# lighthouse_sensor.net
KiCad netlist of a schematic drawn in Altium Designer
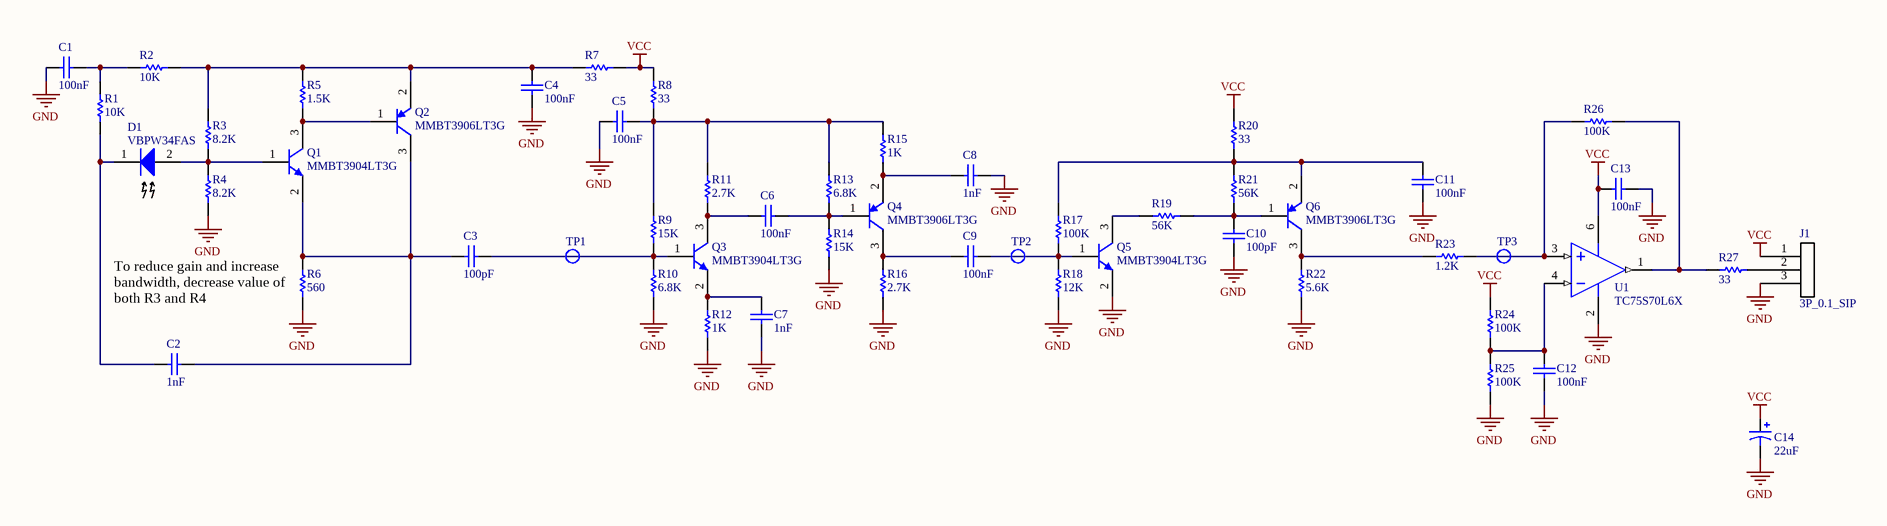
[diagram p0: lighthouse_sensor.SchDoc]

(export (version "E")
  (design (tool "Eeschema 10.0.6"))
  (components
    (comp (ref "C1")
      (value "100nF")
      (footprint "0603")
      (description "Ceramic Chip Capacitor - Standard")
      (fields (field (name "Comment") "C0603") (field (name "PUBLISHER") "Altium Limited"))
      (libsource (lib "lighthouse_sensor") (part "C0603"))
    )
    (comp (ref "C2")
      (value "1nF")
      (footprint "0603")
      (description "Ceramic Chip Capacitor - Standard")
      (fields (field (name "Comment") "C0603") (field (name "PUBLISHER") "Altium Limited"))
      (libsource (lib "lighthouse_sensor") (part "C0603"))
    )
    (comp (ref "C3")
      (value "100pF")
      (footprint "0603")
      (description "Ceramic Chip Capacitor - Standard")
      (fields (field (name "Comment") "C0603") (field (name "PUBLISHER") "Altium Limited"))
      (libsource (lib "lighthouse_sensor") (part "C0603"))
    )
    (comp (ref "C4")
      (value "100nF")
      (footprint "0603")
      (description "Ceramic Chip Capacitor - Standard")
      (fields (field (name "Comment") "C0603") (field (name "PUBLISHER") "Altium Limited"))
      (libsource (lib "lighthouse_sensor") (part "C0603"))
    )
    (comp (ref "C5")
      (value "100nF")
      (footprint "0603")
      (description "Ceramic Chip Capacitor - Standard")
      (fields (field (name "Comment") "C0603") (field (name "PUBLISHER") "Altium Limited"))
      (libsource (lib "lighthouse_sensor") (part "C0603"))
    )
    (comp (ref "C6")
      (value "100nF")
      (footprint "0603")
      (description "Ceramic Chip Capacitor - Standard")
      (fields (field (name "Comment") "C0603") (field (name "PUBLISHER") "Altium Limited"))
      (libsource (lib "lighthouse_sensor") (part "C0603"))
    )
    (comp (ref "C7")
      (value "1nF")
      (footprint "0603")
      (description "Ceramic Chip Capacitor - Standard")
      (fields (field (name "Comment") "C0603") (field (name "PUBLISHER") "Altium Limited"))
      (libsource (lib "lighthouse_sensor") (part "C0603"))
    )
    (comp (ref "C8")
      (value "1nF")
      (footprint "0603")
      (description "Ceramic Chip Capacitor - Standard")
      (fields (field (name "Comment") "C0603") (field (name "PUBLISHER") "Altium Limited"))
      (libsource (lib "lighthouse_sensor") (part "C0603"))
    )
    (comp (ref "C9")
      (value "100nF")
      (footprint "0603")
      (description "Ceramic Chip Capacitor - Standard")
      (fields (field (name "Comment") "C0603") (field (name "PUBLISHER") "Altium Limited"))
      (libsource (lib "lighthouse_sensor") (part "C0603"))
    )
    (comp (ref "C10")
      (value "100pF")
      (footprint "0603")
      (description "Ceramic Chip Capacitor - Standard")
      (fields (field (name "Comment") "C0603") (field (name "PUBLISHER") "Altium Limited"))
      (libsource (lib "lighthouse_sensor") (part "C0603"))
    )
    (comp (ref "C11")
      (value "100nF")
      (footprint "0603")
      (description "Ceramic Chip Capacitor - Standard")
      (fields (field (name "Comment") "C0603") (field (name "PUBLISHER") "Altium Limited"))
      (libsource (lib "lighthouse_sensor") (part "C0603"))
    )
    (comp (ref "C12")
      (value "100nF")
      (footprint "0603")
      (description "Ceramic Chip Capacitor - Standard")
      (fields (field (name "Comment") "C0603") (field (name "PUBLISHER") "Altium Limited"))
      (libsource (lib "lighthouse_sensor") (part "C0603"))
    )
    (comp (ref "C13")
      (value "100nF")
      (footprint "0603")
      (description "Ceramic Chip Capacitor - Standard")
      (fields (field (name "Comment") "C0603") (field (name "PUBLISHER") "Altium Limited"))
      (libsource (lib "lighthouse_sensor") (part "C0603"))
    )
    (comp (ref "C14")
      (value "22uF")
      (footprint "Capacitor")
      (fields (field (name "Comment") "Electrolytic Capacitor"))
      (libsource (lib "lighthouse_sensor") (part "Electrolytic Capacitor"))
    )
    (comp (ref "D1")
      (value "VBPW34FAS")
      (footprint "VBPW34FAS")
      (description "Silicon PIN Photodiode")
      (libsource (lib "lighthouse_sensor") (part "VBPW34FAS"))
    )
    (comp (ref "J1")
      (value "3P_0.1_SIP")
      (footprint "3P_0.1_SIP")
      (description "1x3 0.1\" PTH Header")
      (libsource (lib "lighthouse_sensor") (part "3P_0.1_SIP"))
    )
    (comp (ref "Q1")
      (value "MMBT3904LT3G")
      (footprint "ONSC-SOT-23-3-318-08_V")
      (description "General Purpose Transistor, NPN Silicon, 3-Pin SOT-23, Pb-Free, Tape and Reel")
      (fields (field (name "MANUFACTURER") "On Semiconductor"))
      (libsource (lib "lighthouse_sensor") (part "MMBT3904LT3G"))
    )
    (comp (ref "Q2")
      (value "MMBT3906LT3G")
      (footprint "ONSC-SOT-23-3-318-08_V")
      (description "General Purpose Transistor, PNP Silicon, 3-Pin SOT-23, Pb-Free, Tape and Reel")
      (fields (field (name "MANUFACTURER") "On Semiconductor"))
      (libsource (lib "lighthouse_sensor") (part "MMBT3906LT3G"))
    )
    (comp (ref "Q3")
      (value "MMBT3904LT3G")
      (footprint "ONSC-SOT-23-3-318-08_V")
      (description "General Purpose Transistor, NPN Silicon, 3-Pin SOT-23, Pb-Free, Tape and Reel")
      (fields (field (name "MANUFACTURER") "On Semiconductor"))
      (libsource (lib "lighthouse_sensor") (part "MMBT3904LT3G"))
    )
    (comp (ref "Q4")
      (value "MMBT3906LT3G")
      (footprint "ONSC-SOT-23-3-318-08_V")
      (description "General Purpose Transistor, PNP Silicon, 3-Pin SOT-23, Pb-Free, Tape and Reel")
      (fields (field (name "MANUFACTURER") "On Semiconductor"))
      (libsource (lib "lighthouse_sensor") (part "MMBT3906LT3G"))
    )
    (comp (ref "Q5")
      (value "MMBT3904LT3G")
      (footprint "ONSC-SOT-23-3-318-08_V")
      (description "General Purpose Transistor, NPN Silicon, 3-Pin SOT-23, Pb-Free, Tape and Reel")
      (fields (field (name "MANUFACTURER") "On Semiconductor"))
      (libsource (lib "lighthouse_sensor") (part "MMBT3904LT3G"))
    )
    (comp (ref "Q6")
      (value "MMBT3906LT3G")
      (footprint "ONSC-SOT-23-3-318-08_V")
      (description "General Purpose Transistor, PNP Silicon, 3-Pin SOT-23, Pb-Free, Tape and Reel")
      (fields (field (name "MANUFACTURER") "On Semiconductor"))
      (libsource (lib "lighthouse_sensor") (part "MMBT3906LT3G"))
    )
    (comp (ref "R1")
      (value "10K")
      (footprint "3-0603")
      (fields (field (name "PUBLISHER") "Altium Limited"))
      (libsource (lib "lighthouse_sensor") (part "ERJ3EK"))
    )
    (comp (ref "R2")
      (value "10K")
      (footprint "3-0603")
      (fields (field (name "PUBLISHER") "Altium Limited"))
      (libsource (lib "lighthouse_sensor") (part "ERJ3EK"))
    )
    (comp (ref "R3")
      (value "8.2K")
      (footprint "3-0603")
      (fields (field (name "PUBLISHER") "Altium Limited"))
      (libsource (lib "lighthouse_sensor") (part "ERJ3EK"))
    )
    (comp (ref "R4")
      (value "8.2K")
      (footprint "3-0603")
      (fields (field (name "PUBLISHER") "Altium Limited"))
      (libsource (lib "lighthouse_sensor") (part "ERJ3EK"))
    )
    (comp (ref "R5")
      (value "1.5K")
      (footprint "3-0603")
      (fields (field (name "PUBLISHER") "Altium Limited"))
      (libsource (lib "lighthouse_sensor") (part "ERJ3EK"))
    )
    (comp (ref "R6")
      (value "560")
      (footprint "3-0603")
      (fields (field (name "PUBLISHER") "Altium Limited"))
      (libsource (lib "lighthouse_sensor") (part "ERJ3EK"))
    )
    (comp (ref "R7")
      (value "33")
      (footprint "3-0603")
      (fields (field (name "PUBLISHER") "Altium Limited"))
      (libsource (lib "lighthouse_sensor") (part "ERJ3EK"))
    )
    (comp (ref "R8")
      (value "33")
      (footprint "3-0603")
      (fields (field (name "PUBLISHER") "Altium Limited"))
      (libsource (lib "lighthouse_sensor") (part "ERJ3EK"))
    )
    (comp (ref "R9")
      (value "15K")
      (footprint "3-0603")
      (fields (field (name "PUBLISHER") "Altium Limited"))
      (libsource (lib "lighthouse_sensor") (part "ERJ3EK"))
    )
    (comp (ref "R10")
      (value "6.8K")
      (footprint "3-0603")
      (fields (field (name "PUBLISHER") "Altium Limited"))
      (libsource (lib "lighthouse_sensor") (part "ERJ3EK"))
    )
    (comp (ref "R11")
      (value "2.7K")
      (footprint "3-0603")
      (fields (field (name "PUBLISHER") "Altium Limited"))
      (libsource (lib "lighthouse_sensor") (part "ERJ3EK"))
    )
    (comp (ref "R12")
      (value "1K")
      (footprint "3-0603")
      (fields (field (name "PUBLISHER") "Altium Limited"))
      (libsource (lib "lighthouse_sensor") (part "ERJ3EK"))
    )
    (comp (ref "R13")
      (value "6.8K")
      (footprint "3-0603")
      (fields (field (name "PUBLISHER") "Altium Limited"))
      (libsource (lib "lighthouse_sensor") (part "ERJ3EK"))
    )
    (comp (ref "R14")
      (value "15K")
      (footprint "3-0603")
      (fields (field (name "PUBLISHER") "Altium Limited"))
      (libsource (lib "lighthouse_sensor") (part "ERJ3EK"))
    )
    (comp (ref "R15")
      (value "1K")
      (footprint "3-0603")
      (fields (field (name "PUBLISHER") "Altium Limited"))
      (libsource (lib "lighthouse_sensor") (part "ERJ3EK"))
    )
    (comp (ref "R16")
      (value "2.7K")
      (footprint "3-0603")
      (fields (field (name "PUBLISHER") "Altium Limited"))
      (libsource (lib "lighthouse_sensor") (part "ERJ3EK"))
    )
    (comp (ref "R17")
      (value "100K")
      (footprint "3-0603")
      (fields (field (name "PUBLISHER") "Altium Limited"))
      (libsource (lib "lighthouse_sensor") (part "ERJ3EK"))
    )
    (comp (ref "R18")
      (value "12K")
      (footprint "3-0603")
      (fields (field (name "PUBLISHER") "Altium Limited"))
      (libsource (lib "lighthouse_sensor") (part "ERJ3EK"))
    )
    (comp (ref "R19")
      (value "56K")
      (footprint "3-0603")
      (fields (field (name "PUBLISHER") "Altium Limited"))
      (libsource (lib "lighthouse_sensor") (part "ERJ3EK"))
    )
    (comp (ref "R20")
      (value "33")
      (footprint "3-0603")
      (fields (field (name "PUBLISHER") "Altium Limited"))
      (libsource (lib "lighthouse_sensor") (part "ERJ3EK"))
    )
    (comp (ref "R21")
      (value "56K")
      (footprint "3-0603")
      (fields (field (name "PUBLISHER") "Altium Limited"))
      (libsource (lib "lighthouse_sensor") (part "ERJ3EK"))
    )
    (comp (ref "R22")
      (value "5.6K")
      (footprint "3-0603")
      (fields (field (name "PUBLISHER") "Altium Limited"))
      (libsource (lib "lighthouse_sensor") (part "ERJ3EK"))
    )
    (comp (ref "R23")
      (value "1.2K")
      (footprint "3-0603")
      (fields (field (name "PUBLISHER") "Altium Limited"))
      (libsource (lib "lighthouse_sensor") (part "ERJ3EK"))
    )
    (comp (ref "R24")
      (value "100K")
      (footprint "3-0603")
      (fields (field (name "PUBLISHER") "Altium Limited"))
      (libsource (lib "lighthouse_sensor") (part "ERJ3EK"))
    )
    (comp (ref "R25")
      (value "100K")
      (footprint "3-0603")
      (fields (field (name "PUBLISHER") "Altium Limited"))
      (libsource (lib "lighthouse_sensor") (part "ERJ3EK"))
    )
    (comp (ref "R26")
      (value "100K")
      (footprint "3-0603")
      (fields (field (name "PUBLISHER") "Altium Limited"))
      (libsource (lib "lighthouse_sensor") (part "ERJ3EK"))
    )
    (comp (ref "R27")
      (value "33")
      (footprint "3-0603")
      (fields (field (name "PUBLISHER") "Altium Limited"))
      (libsource (lib "lighthouse_sensor") (part "ERJ3EK"))
    )
    (comp (ref "U1")
      (value "TC75S70L6X")
      (footprint "MP6C")
      (description "Single Comparator")
      (libsource (lib "lighthouse_sensor") (part "TC75S70L6X"))
    )
  )
  (nets
    (net (code "1") (name "GND") (class "Default")
      (node (ref "C1") (pin "2") (pinfunction "2_2") (pintype "passive"))
      (node (ref "C10") (pin "2") (pinfunction "2_2") (pintype "passive"))
      (node (ref "C11") (pin "2") (pinfunction "2_2") (pintype "passive"))
      (node (ref "C12") (pin "2") (pinfunction "2_2") (pintype "passive"))
      (node (ref "C13") (pin "1") (pinfunction "1_1") (pintype "passive"))
      (node (ref "C14") (pin "2") (pinfunction "2_2") (pintype "passive"))
      (node (ref "C4") (pin "2") (pinfunction "2_2") (pintype "passive"))
      (node (ref "C5") (pin "2") (pinfunction "2_2") (pintype "passive"))
      (node (ref "C7") (pin "2") (pinfunction "2_2") (pintype "passive"))
      (node (ref "C8") (pin "1") (pinfunction "1_1") (pintype "passive"))
      (node (ref "J1") (pin "3") (pinfunction "3_3") (pintype "passive"))
      (node (ref "Q5") (pin "2") (pinfunction "E_2") (pintype "passive"))
      (node (ref "R10") (pin "1") (pinfunction "1_1") (pintype "passive"))
      (node (ref "R12") (pin "1") (pinfunction "1_1") (pintype "passive"))
      (node (ref "R14") (pin "1") (pinfunction "1_1") (pintype "passive"))
      (node (ref "R16") (pin "1") (pinfunction "1_1") (pintype "passive"))
      (node (ref "R18") (pin "1") (pinfunction "1_1") (pintype "passive"))
      (node (ref "R22") (pin "1") (pinfunction "1_1") (pintype "passive"))
      (node (ref "R25") (pin "1") (pinfunction "1_1") (pintype "passive"))
      (node (ref "R4") (pin "1") (pinfunction "1_1") (pintype "passive"))
      (node (ref "R6") (pin "1") (pinfunction "1_1") (pintype "passive"))
      (node (ref "U1") (pin "2") (pinfunction "VSS_2") (pintype "power_in"))
    )
    (net (code "2") (name "Net-(C1-Pad1)") (class "Default")
      (node (ref "C1") (pin "1") (pinfunction "1_1") (pintype "passive"))
      (node (ref "R1") (pin "2") (pinfunction "2_2") (pintype "passive"))
      (node (ref "R2") (pin "2") (pinfunction "2_2") (pintype "passive"))
    )
    (net (code "3") (name "Net-(C5-Pad1)") (class "Default")
      (node (ref "C5") (pin "1") (pinfunction "1_1") (pintype "passive"))
      (node (ref "R11") (pin "1") (pinfunction "1_1") (pintype "passive"))
      (node (ref "R13") (pin "1") (pinfunction "1_1") (pintype "passive"))
      (node (ref "R15") (pin "1") (pinfunction "1_1") (pintype "passive"))
      (node (ref "R8") (pin "2") (pinfunction "2_2") (pintype "passive"))
      (node (ref "R9") (pin "1") (pinfunction "1_1") (pintype "passive"))
    )
    (net (code "4") (name "Net-(D1-A)") (class "Default")
      (node (ref "D1") (pin "2") (pinfunction "A_2") (pintype "passive"))
      (node (ref "Q1") (pin "1") (pinfunction "B_1") (pintype "passive"))
      (node (ref "R3") (pin "1") (pinfunction "1_1") (pintype "passive"))
      (node (ref "R4") (pin "2") (pinfunction "2_2") (pintype "passive"))
    )
    (net (code "5") (name "Net-(D1-K)") (class "Default")
      (node (ref "C2") (pin "2") (pinfunction "2_2") (pintype "passive"))
      (node (ref "D1") (pin "1") (pinfunction "K_1") (pintype "passive"))
      (node (ref "R1") (pin "1") (pinfunction "1_1") (pintype "passive"))
    )
    (net (code "6") (name "Net-(J1-Pad2)") (class "Default")
      (node (ref "J1") (pin "2") (pinfunction "2_2") (pintype "passive"))
      (node (ref "R27") (pin "1") (pinfunction "1_1") (pintype "passive"))
    )
    (net (code "7") (name "Net-(Q1-C)") (class "Default")
      (node (ref "Q1") (pin "3") (pinfunction "C_3") (pintype "passive"))
      (node (ref "Q2") (pin "1") (pinfunction "B_1") (pintype "passive"))
      (node (ref "R5") (pin "1") (pinfunction "1_1") (pintype "passive"))
    )
    (net (code "8") (name "Net-(Q1-E)") (class "Default")
      (node (ref "C2") (pin "1") (pinfunction "1_1") (pintype "passive"))
      (node (ref "C3") (pin "2") (pinfunction "2_2") (pintype "passive"))
      (node (ref "Q1") (pin "2") (pinfunction "E_2") (pintype "passive"))
      (node (ref "Q2") (pin "3") (pinfunction "C_3") (pintype "passive"))
      (node (ref "R6") (pin "2") (pinfunction "2_2") (pintype "passive"))
    )
    (net (code "9") (name "Net-(Q2-E)") (class "Default")
      (node (ref "C4") (pin "1") (pinfunction "1_1") (pintype "passive"))
      (node (ref "Q2") (pin "2") (pinfunction "E_2") (pintype "passive"))
      (node (ref "R2") (pin "1") (pinfunction "1_1") (pintype "passive"))
      (node (ref "R3") (pin "2") (pinfunction "2_2") (pintype "passive"))
      (node (ref "R5") (pin "2") (pinfunction "2_2") (pintype "passive"))
      (node (ref "R7") (pin "2") (pinfunction "2_2") (pintype "passive"))
    )
    (net (code "10") (name "Net-(Q3-B)") (class "Default")
      (node (ref "C3") (pin "1") (pinfunction "1_1") (pintype "passive"))
      (node (ref "Q3") (pin "1") (pinfunction "B_1") (pintype "passive"))
      (node (ref "R10") (pin "2") (pinfunction "2_2") (pintype "passive"))
      (node (ref "R9") (pin "2") (pinfunction "2_2") (pintype "passive"))
    )
    (net (code "11") (name "Net-(Q3-C)") (class "Default")
      (node (ref "C6") (pin "2") (pinfunction "2_2") (pintype "passive"))
      (node (ref "Q3") (pin "3") (pinfunction "C_3") (pintype "passive"))
      (node (ref "R11") (pin "2") (pinfunction "2_2") (pintype "passive"))
    )
    (net (code "12") (name "Net-(Q3-E)") (class "Default")
      (node (ref "C7") (pin "1") (pinfunction "1_1") (pintype "passive"))
      (node (ref "Q3") (pin "2") (pinfunction "E_2") (pintype "passive"))
      (node (ref "R12") (pin "2") (pinfunction "2_2") (pintype "passive"))
    )
    (net (code "13") (name "Net-(Q4-B)") (class "Default")
      (node (ref "C6") (pin "1") (pinfunction "1_1") (pintype "passive"))
      (node (ref "Q4") (pin "1") (pinfunction "B_1") (pintype "passive"))
      (node (ref "R13") (pin "2") (pinfunction "2_2") (pintype "passive"))
      (node (ref "R14") (pin "2") (pinfunction "2_2") (pintype "passive"))
    )
    (net (code "14") (name "Net-(Q4-C)") (class "Default")
      (node (ref "C9") (pin "2") (pinfunction "2_2") (pintype "passive"))
      (node (ref "Q4") (pin "3") (pinfunction "C_3") (pintype "passive"))
      (node (ref "R16") (pin "2") (pinfunction "2_2") (pintype "passive"))
    )
    (net (code "15") (name "Net-(Q4-E)") (class "Default")
      (node (ref "C8") (pin "2") (pinfunction "2_2") (pintype "passive"))
      (node (ref "Q4") (pin "2") (pinfunction "E_2") (pintype "passive"))
      (node (ref "R15") (pin "2") (pinfunction "2_2") (pintype "passive"))
    )
    (net (code "16") (name "Net-(Q5-B)") (class "Default")
      (node (ref "C9") (pin "1") (pinfunction "1_1") (pintype "passive"))
      (node (ref "Q5") (pin "1") (pinfunction "B_1") (pintype "passive"))
      (node (ref "R17") (pin "2") (pinfunction "2_2") (pintype "passive"))
      (node (ref "R18") (pin "2") (pinfunction "2_2") (pintype "passive"))
    )
    (net (code "17") (name "Net-(Q5-C)") (class "Default")
      (node (ref "Q5") (pin "3") (pinfunction "C_3") (pintype "passive"))
      (node (ref "R19") (pin "1") (pinfunction "1_1") (pintype "passive"))
    )
    (net (code "18") (name "Net-(Q6-B)") (class "Default")
      (node (ref "C10") (pin "1") (pinfunction "1_1") (pintype "passive"))
      (node (ref "Q6") (pin "1") (pinfunction "B_1") (pintype "passive"))
      (node (ref "R19") (pin "2") (pinfunction "2_2") (pintype "passive"))
      (node (ref "R21") (pin "2") (pinfunction "2_2") (pintype "passive"))
    )
    (net (code "19") (name "Net-(Q6-C)") (class "Default")
      (node (ref "Q6") (pin "3") (pinfunction "C_3") (pintype "passive"))
      (node (ref "R22") (pin "2") (pinfunction "2_2") (pintype "passive"))
      (node (ref "R23") (pin "2") (pinfunction "2_2") (pintype "passive"))
    )
    (net (code "20") (name "Net-(Q6-E)") (class "Default")
      (node (ref "C11") (pin "1") (pinfunction "1_1") (pintype "passive"))
      (node (ref "Q6") (pin "2") (pinfunction "E_2") (pintype "passive"))
      (node (ref "R17") (pin "1") (pinfunction "1_1") (pintype "passive"))
      (node (ref "R20") (pin "2") (pinfunction "2_2") (pintype "passive"))
      (node (ref "R21") (pin "1") (pinfunction "1_1") (pintype "passive"))
    )
    (net (code "21") (name "Net-(U1-+IN)") (class "Default")
      (node (ref "R23") (pin "1") (pinfunction "1_1") (pintype "passive"))
      (node (ref "R26") (pin "2") (pinfunction "2_2") (pintype "passive"))
      (node (ref "U1") (pin "3") (pinfunction "+IN_3") (pintype "input"))
    )
    (net (code "22") (name "Net-(U1--IN)") (class "Default")
      (node (ref "C12") (pin "1") (pinfunction "1_1") (pintype "passive"))
      (node (ref "R24") (pin "2") (pinfunction "2_2") (pintype "passive"))
      (node (ref "R25") (pin "2") (pinfunction "2_2") (pintype "passive"))
      (node (ref "U1") (pin "4") (pinfunction "-IN_4") (pintype "input"))
    )
    (net (code "23") (name "Net-(U1-OUT)") (class "Default")
      (node (ref "R26") (pin "1") (pinfunction "1_1") (pintype "passive"))
      (node (ref "R27") (pin "2") (pinfunction "2_2") (pintype "passive"))
      (node (ref "U1") (pin "1") (pinfunction "OUT_1") (pintype "output"))
    )
    (net (code "24") (name "VCC") (class "Default")
      (node (ref "C13") (pin "2") (pinfunction "2_2") (pintype "passive"))
      (node (ref "C14") (pin "1") (pinfunction "1_1") (pintype "passive"))
      (node (ref "J1") (pin "1") (pinfunction "1_1") (pintype "passive"))
      (node (ref "R20") (pin "1") (pinfunction "1_1") (pintype "passive"))
      (node (ref "R24") (pin "1") (pinfunction "1_1") (pintype "passive"))
      (node (ref "R7") (pin "1") (pinfunction "1_1") (pintype "passive"))
      (node (ref "R8") (pin "1") (pinfunction "1_1") (pintype "passive"))
      (node (ref "U1") (pin "6") (pinfunction "VDD_6") (pintype "power_in"))
    )
  )
)
